# LEDmeterboard.net
KiCad netlist of a schematic drawn in EAGLE
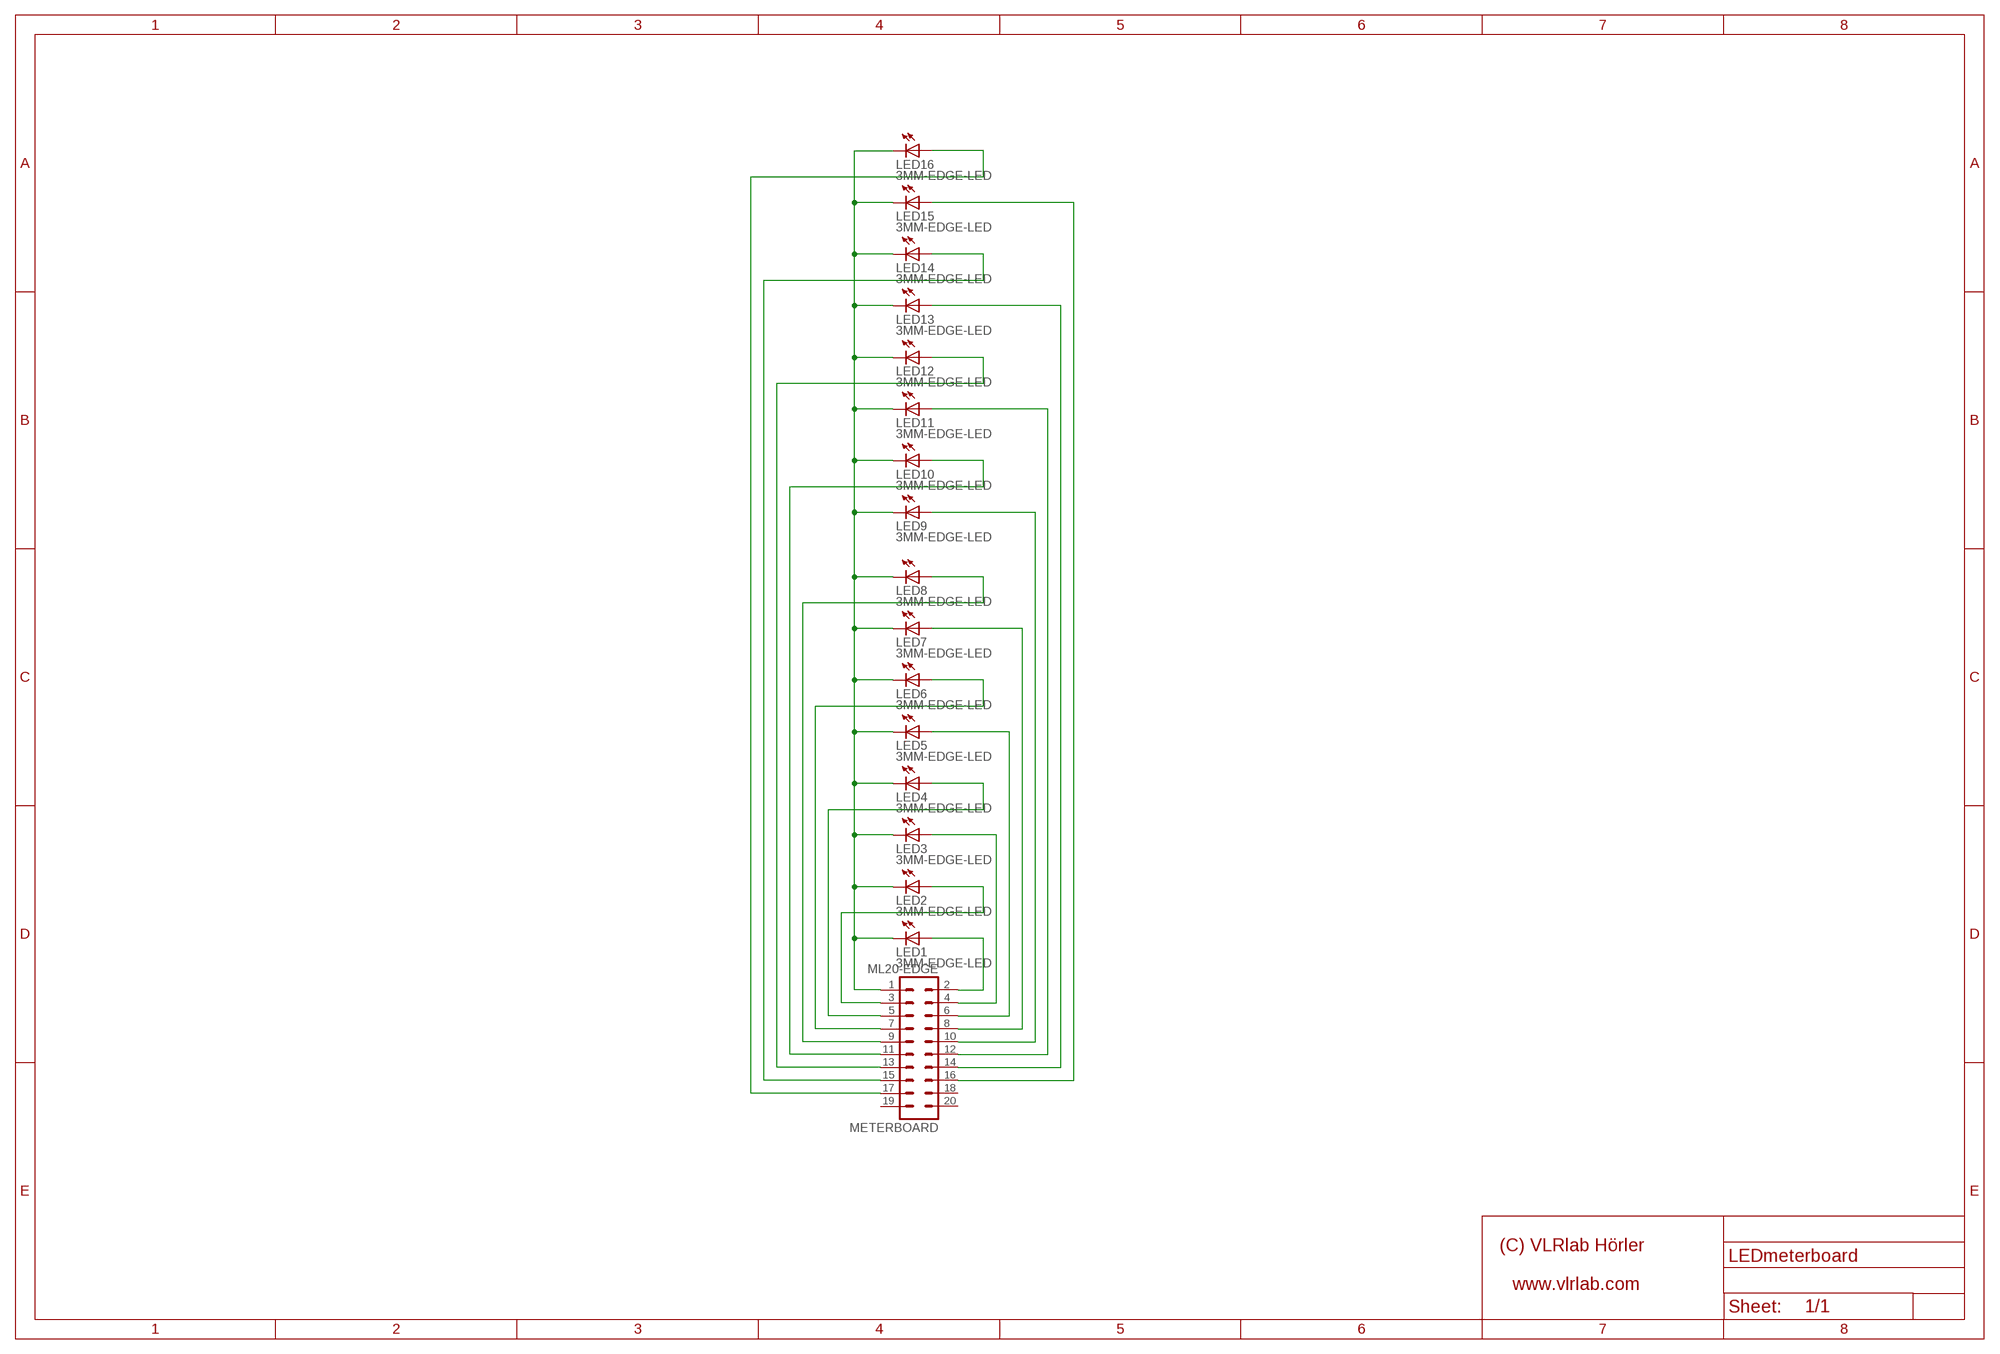
[diagram p0: schematic, sheet 1]

(export (version "E")
  (design (tool "Eeschema 10.0.6"))
  (components
    (comp (ref "LED1")
      (value "3MM-EDGE-LED")
      (footprint "eagle-import:3MM-EDGE-LED")
      (libsource (lib "eagle-import") (part "3MM-EDGE-LED"))
    )
    (comp (ref "LED2")
      (value "3MM-EDGE-LED")
      (footprint "eagle-import:3MM-EDGE-LED")
      (libsource (lib "eagle-import") (part "3MM-EDGE-LED"))
    )
    (comp (ref "LED3")
      (value "3MM-EDGE-LED")
      (footprint "eagle-import:3MM-EDGE-LED")
      (libsource (lib "eagle-import") (part "3MM-EDGE-LED"))
    )
    (comp (ref "LED4")
      (value "3MM-EDGE-LED")
      (footprint "eagle-import:3MM-EDGE-LED")
      (libsource (lib "eagle-import") (part "3MM-EDGE-LED"))
    )
    (comp (ref "LED5")
      (value "3MM-EDGE-LED")
      (footprint "eagle-import:3MM-EDGE-LED")
      (libsource (lib "eagle-import") (part "3MM-EDGE-LED"))
    )
    (comp (ref "LED6")
      (value "3MM-EDGE-LED")
      (footprint "eagle-import:3MM-EDGE-LED")
      (libsource (lib "eagle-import") (part "3MM-EDGE-LED"))
    )
    (comp (ref "LED7")
      (value "3MM-EDGE-LED")
      (footprint "eagle-import:3MM-EDGE-LED")
      (libsource (lib "eagle-import") (part "3MM-EDGE-LED"))
    )
    (comp (ref "LED8")
      (value "3MM-EDGE-LED")
      (footprint "eagle-import:3MM-EDGE-LED")
      (libsource (lib "eagle-import") (part "3MM-EDGE-LED"))
    )
    (comp (ref "LED9")
      (value "3MM-EDGE-LED")
      (footprint "eagle-import:3MM-EDGE-LED")
      (libsource (lib "eagle-import") (part "3MM-EDGE-LED"))
    )
    (comp (ref "LED10")
      (value "3MM-EDGE-LED")
      (footprint "eagle-import:3MM-EDGE-LED")
      (libsource (lib "eagle-import") (part "3MM-EDGE-LED"))
    )
    (comp (ref "LED11")
      (value "3MM-EDGE-LED")
      (footprint "eagle-import:3MM-EDGE-LED")
      (libsource (lib "eagle-import") (part "3MM-EDGE-LED"))
    )
    (comp (ref "LED12")
      (value "3MM-EDGE-LED")
      (footprint "eagle-import:3MM-EDGE-LED")
      (libsource (lib "eagle-import") (part "3MM-EDGE-LED"))
    )
    (comp (ref "LED13")
      (value "3MM-EDGE-LED")
      (footprint "eagle-import:3MM-EDGE-LED")
      (libsource (lib "eagle-import") (part "3MM-EDGE-LED"))
    )
    (comp (ref "LED14")
      (value "3MM-EDGE-LED")
      (footprint "eagle-import:3MM-EDGE-LED")
      (libsource (lib "eagle-import") (part "3MM-EDGE-LED"))
    )
    (comp (ref "LED15")
      (value "3MM-EDGE-LED")
      (footprint "eagle-import:3MM-EDGE-LED")
      (libsource (lib "eagle-import") (part "3MM-EDGE-LED"))
    )
    (comp (ref "LED16")
      (value "3MM-EDGE-LED")
      (footprint "eagle-import:3MM-EDGE-LED")
      (libsource (lib "eagle-import") (part "3MM-EDGE-LED"))
    )
    (comp (ref "METERBOARD")
      (value "ML20-EDGE")
      (footprint "eagle-import:ML20EDGE")
      (libsource (lib "eagle-import") (part "ML20-EDGE"))
    )
  )
  (nets
    (net (code "1") (name "Net-(LED1-A)") (class "Default")
      (node (ref "LED1") (pin "ANODE") (pinfunction "A_ANODE") (pintype "passive"))
      (node (ref "METERBOARD") (pin "2") (pinfunction "2_2") (pintype "passive"))
    )
    (net (code "2") (name "Net-(LED1-C)") (class "Default")
      (node (ref "LED1") (pin "KATHODE") (pinfunction "C_KATHODE") (pintype "passive"))
      (node (ref "LED10") (pin "KATHODE") (pinfunction "C_KATHODE") (pintype "passive"))
      (node (ref "LED11") (pin "KATHODE") (pinfunction "C_KATHODE") (pintype "passive"))
      (node (ref "LED12") (pin "KATHODE") (pinfunction "C_KATHODE") (pintype "passive"))
      (node (ref "LED13") (pin "KATHODE") (pinfunction "C_KATHODE") (pintype "passive"))
      (node (ref "LED14") (pin "KATHODE") (pinfunction "C_KATHODE") (pintype "passive"))
      (node (ref "LED15") (pin "KATHODE") (pinfunction "C_KATHODE") (pintype "passive"))
      (node (ref "LED16") (pin "KATHODE") (pinfunction "C_KATHODE") (pintype "passive"))
      (node (ref "LED2") (pin "KATHODE") (pinfunction "C_KATHODE") (pintype "passive"))
      (node (ref "LED3") (pin "KATHODE") (pinfunction "C_KATHODE") (pintype "passive"))
      (node (ref "LED4") (pin "KATHODE") (pinfunction "C_KATHODE") (pintype "passive"))
      (node (ref "LED5") (pin "KATHODE") (pinfunction "C_KATHODE") (pintype "passive"))
      (node (ref "LED6") (pin "KATHODE") (pinfunction "C_KATHODE") (pintype "passive"))
      (node (ref "LED7") (pin "KATHODE") (pinfunction "C_KATHODE") (pintype "passive"))
      (node (ref "LED8") (pin "KATHODE") (pinfunction "C_KATHODE") (pintype "passive"))
      (node (ref "LED9") (pin "KATHODE") (pinfunction "C_KATHODE") (pintype "passive"))
      (node (ref "METERBOARD") (pin "1") (pinfunction "1_1") (pintype "passive"))
    )
    (net (code "3") (name "Net-(LED2-A)") (class "Default")
      (node (ref "LED2") (pin "ANODE") (pinfunction "A_ANODE") (pintype "passive"))
      (node (ref "METERBOARD") (pin "3") (pinfunction "3_3") (pintype "passive"))
    )
    (net (code "4") (name "Net-(LED3-A)") (class "Default")
      (node (ref "LED3") (pin "ANODE") (pinfunction "A_ANODE") (pintype "passive"))
      (node (ref "METERBOARD") (pin "4") (pinfunction "4_4") (pintype "passive"))
    )
    (net (code "5") (name "Net-(LED4-A)") (class "Default")
      (node (ref "LED4") (pin "ANODE") (pinfunction "A_ANODE") (pintype "passive"))
      (node (ref "METERBOARD") (pin "5") (pinfunction "5_5") (pintype "passive"))
    )
    (net (code "6") (name "Net-(LED5-A)") (class "Default")
      (node (ref "LED5") (pin "ANODE") (pinfunction "A_ANODE") (pintype "passive"))
      (node (ref "METERBOARD") (pin "6") (pinfunction "6_6") (pintype "passive"))
    )
    (net (code "7") (name "Net-(LED6-A)") (class "Default")
      (node (ref "LED6") (pin "ANODE") (pinfunction "A_ANODE") (pintype "passive"))
      (node (ref "METERBOARD") (pin "7") (pinfunction "7_7") (pintype "passive"))
    )
    (net (code "8") (name "Net-(LED7-A)") (class "Default")
      (node (ref "LED7") (pin "ANODE") (pinfunction "A_ANODE") (pintype "passive"))
      (node (ref "METERBOARD") (pin "8") (pinfunction "8_8") (pintype "passive"))
    )
    (net (code "9") (name "Net-(LED8-A)") (class "Default")
      (node (ref "LED8") (pin "ANODE") (pinfunction "A_ANODE") (pintype "passive"))
      (node (ref "METERBOARD") (pin "9") (pinfunction "9_9") (pintype "passive"))
    )
    (net (code "10") (name "Net-(LED9-A)") (class "Default")
      (node (ref "LED9") (pin "ANODE") (pinfunction "A_ANODE") (pintype "passive"))
      (node (ref "METERBOARD") (pin "10") (pinfunction "10_10") (pintype "passive"))
    )
    (net (code "11") (name "Net-(LED10-A)") (class "Default")
      (node (ref "LED10") (pin "ANODE") (pinfunction "A_ANODE") (pintype "passive"))
      (node (ref "METERBOARD") (pin "11") (pinfunction "11_11") (pintype "passive"))
    )
    (net (code "12") (name "Net-(LED11-A)") (class "Default")
      (node (ref "LED11") (pin "ANODE") (pinfunction "A_ANODE") (pintype "passive"))
      (node (ref "METERBOARD") (pin "12") (pinfunction "12_12") (pintype "passive"))
    )
    (net (code "13") (name "Net-(LED12-A)") (class "Default")
      (node (ref "LED12") (pin "ANODE") (pinfunction "A_ANODE") (pintype "passive"))
      (node (ref "METERBOARD") (pin "13") (pinfunction "13_13") (pintype "passive"))
    )
    (net (code "14") (name "Net-(LED13-A)") (class "Default")
      (node (ref "LED13") (pin "ANODE") (pinfunction "A_ANODE") (pintype "passive"))
      (node (ref "METERBOARD") (pin "14") (pinfunction "14_14") (pintype "passive"))
    )
    (net (code "15") (name "Net-(LED14-A)") (class "Default")
      (node (ref "LED14") (pin "ANODE") (pinfunction "A_ANODE") (pintype "passive"))
      (node (ref "METERBOARD") (pin "15") (pinfunction "15_15") (pintype "passive"))
    )
    (net (code "16") (name "Net-(LED15-A)") (class "Default")
      (node (ref "LED15") (pin "ANODE") (pinfunction "A_ANODE") (pintype "passive"))
      (node (ref "METERBOARD") (pin "16") (pinfunction "16_16") (pintype "passive"))
    )
    (net (code "17") (name "Net-(LED16-A)") (class "Default")
      (node (ref "LED16") (pin "ANODE") (pinfunction "A_ANODE") (pintype "passive"))
      (node (ref "METERBOARD") (pin "17") (pinfunction "17_17") (pintype "passive"))
    )
    (net (code "18") (name "unconnected-(METERBOARD-Pad18)") (class "Default")
      (node (ref "METERBOARD") (pin "18") (pinfunction "18_18") (pintype "passive"))
    )
    (net (code "19") (name "unconnected-(METERBOARD-Pad19)") (class "Default")
      (node (ref "METERBOARD") (pin "19") (pinfunction "19_19") (pintype "passive"))
    )
    (net (code "20") (name "unconnected-(METERBOARD-Pad20)") (class "Default")
      (node (ref "METERBOARD") (pin "20") (pinfunction "20_20") (pintype "passive"))
    )
  )
)
